# InterceptorRS232.net
KiCad netlist of a schematic drawn in Altium Designer
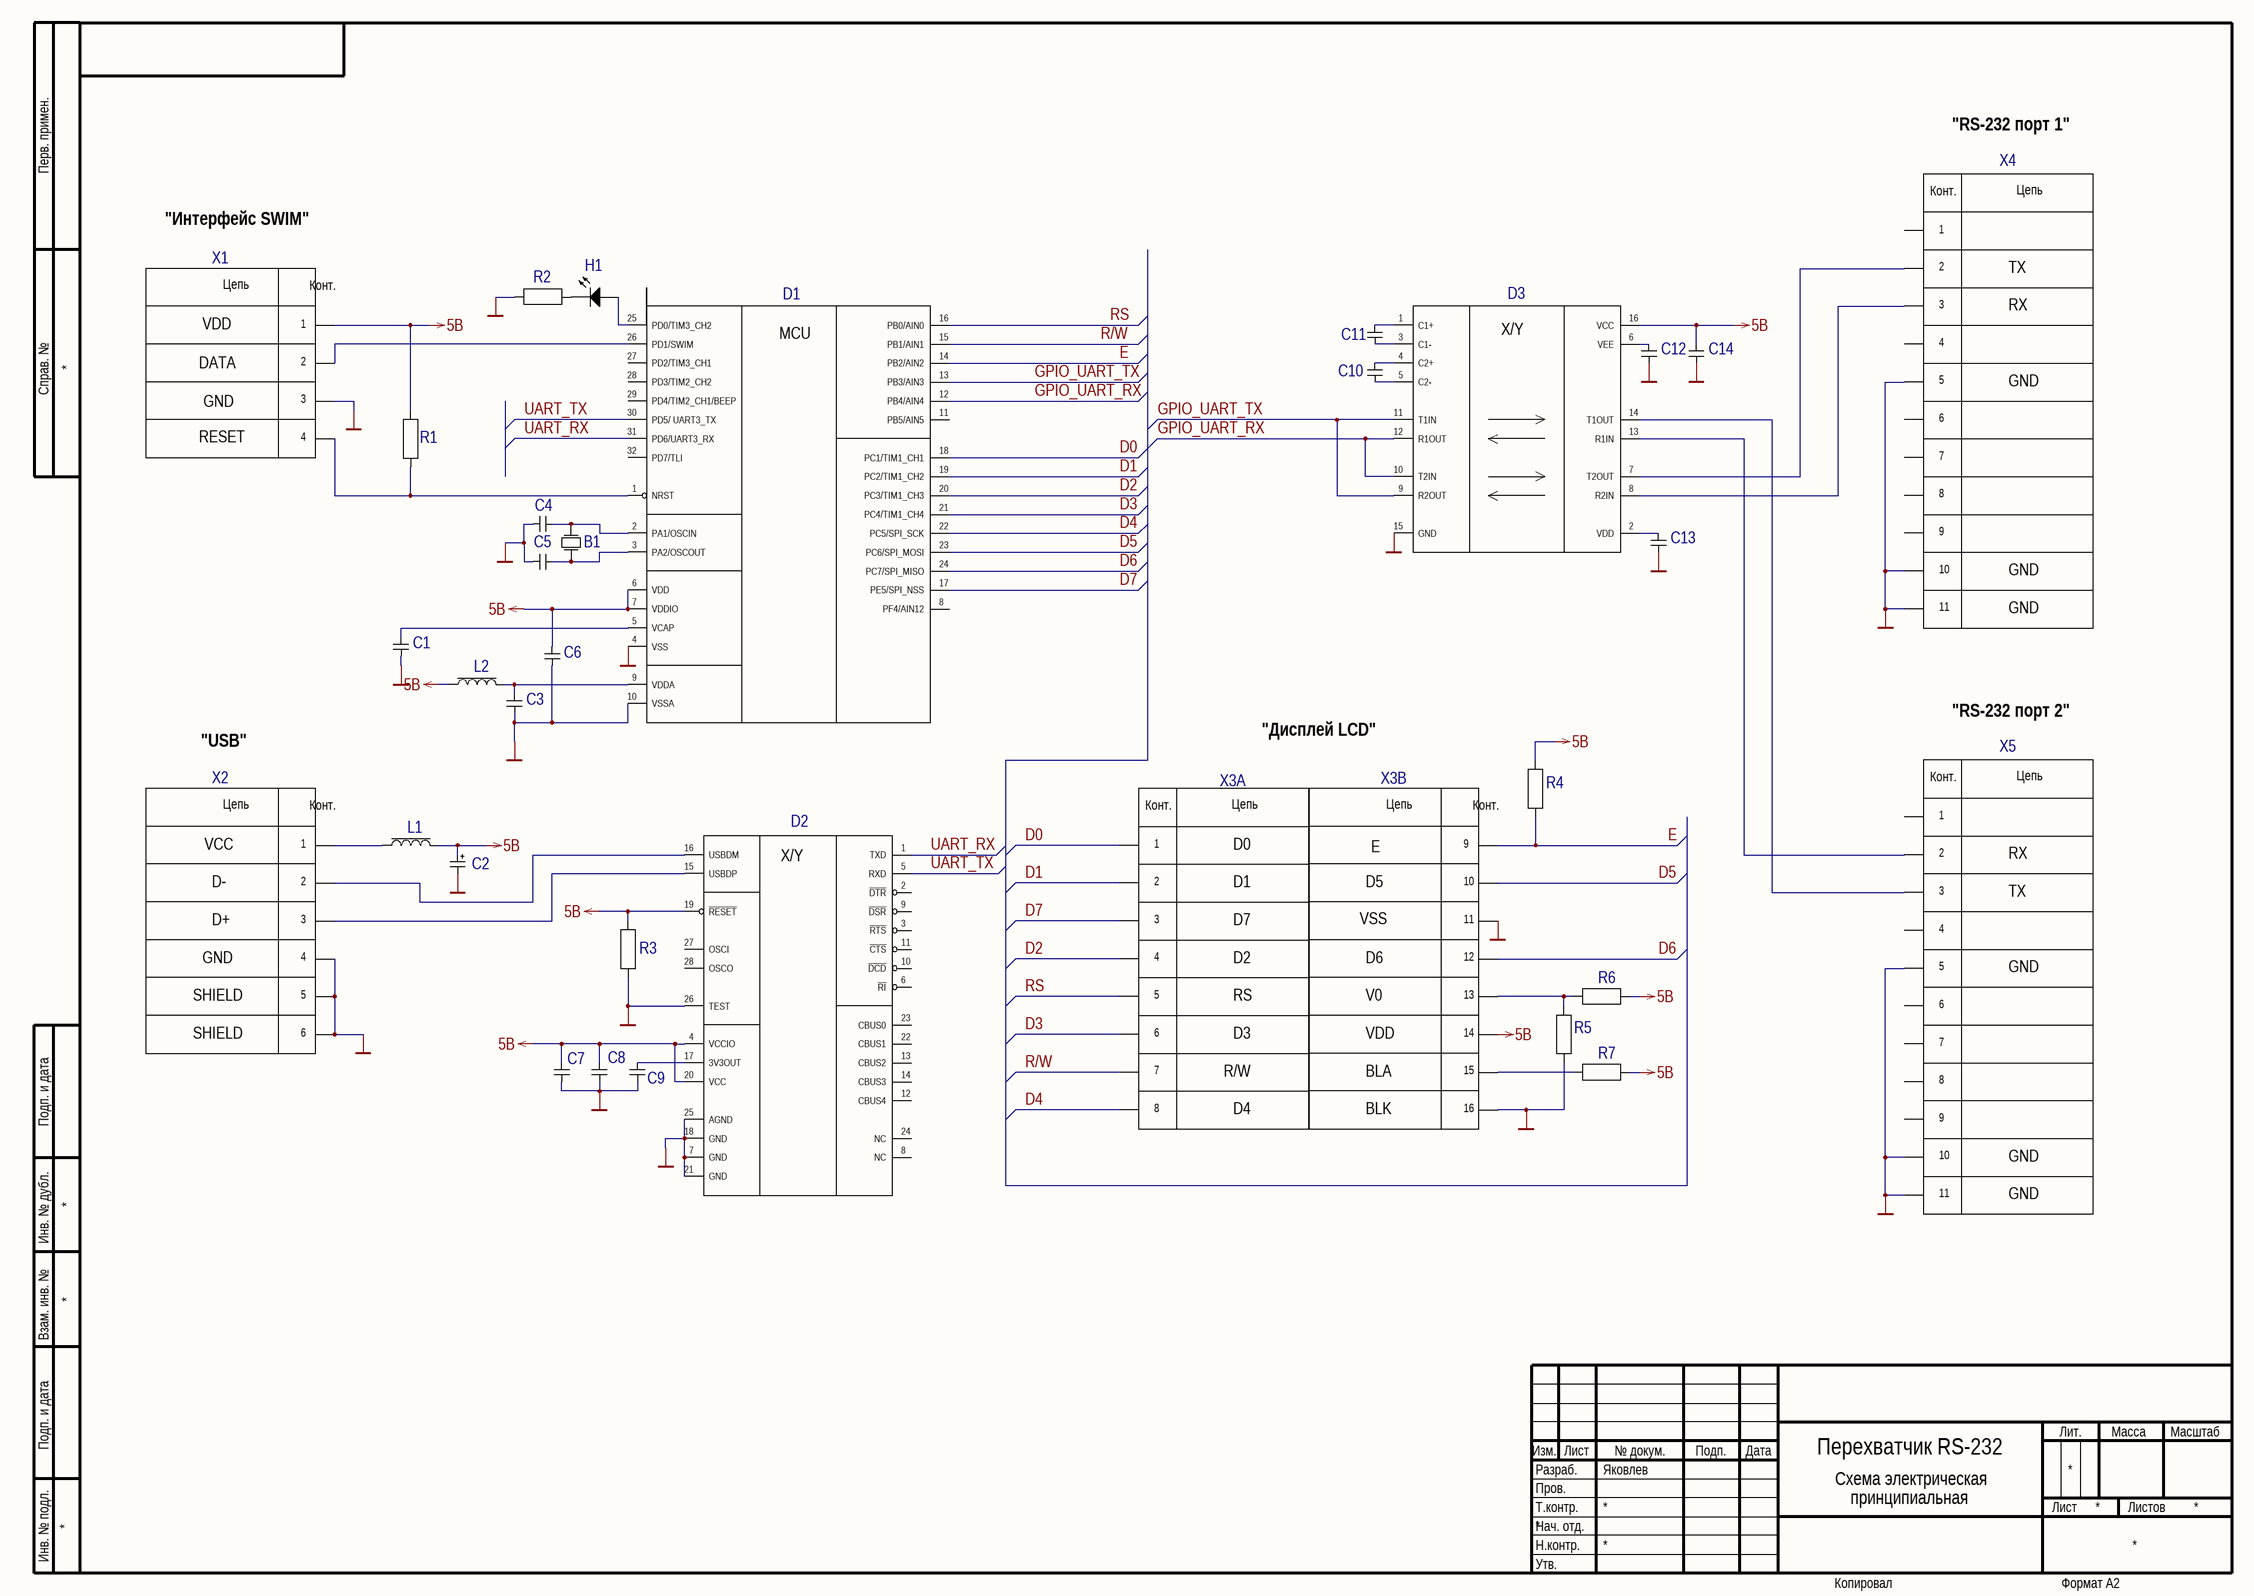
[diagram p0: InterceptorRS232.SchDoc]

(export (version "E")
  (design (tool "Eeschema 10.0.6"))
  (components
    (comp (ref "B1")
      (value "*")
      (footprint "CSM-7")
      (description "Crystal oscillator")
      (libsource (lib "InterceptorRS232") (part "CRYSTAL_OSCILLATOR"))
    )
    (comp (ref "C1")
      (value "~")
      (footprint "SMD-0805C")
      (description "Capacitor")
      (fields (field (name "PUBLISHER") "Altium Limited"))
      (libsource (lib "InterceptorRS232") (part "Cap"))
    )
    (comp (ref "C2")
      (value "Cap_el")
      (footprint "CAP_5x11")
      (description "Electrolytic capacitor")
      (fields (field (name "PUBLISHER") "Altium Limited"))
      (libsource (lib "InterceptorRS232") (part "Cap_el"))
    )
    (comp (ref "C3")
      (value "~")
      (footprint "SMD-0805C")
      (description "Capacitor")
      (fields (field (name "PUBLISHER") "Altium Limited"))
      (libsource (lib "InterceptorRS232") (part "Cap"))
    )
    (comp (ref "C4")
      (value "~")
      (footprint "SMD-0805C")
      (description "Capacitor")
      (fields (field (name "PUBLISHER") "Altium Limited"))
      (libsource (lib "InterceptorRS232") (part "Cap"))
    )
    (comp (ref "C5")
      (value "~")
      (footprint "SMD-0805C")
      (description "Capacitor")
      (fields (field (name "PUBLISHER") "Altium Limited"))
      (libsource (lib "InterceptorRS232") (part "Cap"))
    )
    (comp (ref "C6")
      (value "~")
      (footprint "SMD-0805C")
      (description "Capacitor")
      (fields (field (name "PUBLISHER") "Altium Limited"))
      (libsource (lib "InterceptorRS232") (part "Cap"))
    )
    (comp (ref "C7")
      (value "~")
      (footprint "SMD-0805C")
      (description "Capacitor")
      (fields (field (name "PUBLISHER") "Altium Limited"))
      (libsource (lib "InterceptorRS232") (part "Cap"))
    )
    (comp (ref "C8")
      (value "~")
      (footprint "SMD-0805C")
      (description "Capacitor")
      (fields (field (name "PUBLISHER") "Altium Limited"))
      (libsource (lib "InterceptorRS232") (part "Cap"))
    )
    (comp (ref "C9")
      (value "~")
      (footprint "SMD-0805C")
      (description "Capacitor")
      (fields (field (name "PUBLISHER") "Altium Limited"))
      (libsource (lib "InterceptorRS232") (part "Cap"))
    )
    (comp (ref "C10")
      (value "~")
      (footprint "SMD-0805C")
      (description "Capacitor")
      (fields (field (name "PUBLISHER") "Altium Limited"))
      (libsource (lib "InterceptorRS232") (part "Cap"))
    )
    (comp (ref "C11")
      (value "~")
      (footprint "SMD-0805C")
      (description "Capacitor")
      (fields (field (name "PUBLISHER") "Altium Limited"))
      (libsource (lib "InterceptorRS232") (part "Cap"))
    )
    (comp (ref "C12")
      (value "~")
      (footprint "SMD-0805C")
      (description "Capacitor")
      (fields (field (name "PUBLISHER") "Altium Limited"))
      (libsource (lib "InterceptorRS232") (part "Cap"))
    )
    (comp (ref "C13")
      (value "~")
      (footprint "SMD-0805C")
      (description "Capacitor")
      (fields (field (name "PUBLISHER") "Altium Limited"))
      (libsource (lib "InterceptorRS232") (part "Cap"))
    )
    (comp (ref "C14")
      (value "~")
      (footprint "SMD-0805C")
      (description "Capacitor")
      (fields (field (name "PUBLISHER") "Altium Limited"))
      (libsource (lib "InterceptorRS232") (part "Cap"))
    )
    (comp (ref "D1")
      (value "STM8S207K6T6C")
      (footprint "TQFP32_M")
      (description "8-bit STM8 MCU")
      (libsource (lib "InterceptorRS232") (part "STM8S207/STM8S208"))
    )
    (comp (ref "D2")
      (value "FT232RL-Reel")
      (footprint "SSOP-28_M")
      (description "USB UART Asynchronous Serial Data Transfer Chip, SSOP-28, Tape and Reel")
      (fields (field (name "PUBLISHER") "Altium Limited"))
      (libsource (lib "InterceptorRS232") (part "FT232RL-Reel"))
    )
    (comp (ref "D3")
      (value "MAX232EWE")
      (footprint "SOP-16 (2.54 mm)")
      (description "+5V Powered RS-232 Driver/Receiver")
      (fields (field (name "PUBLISHER") "Altium Limited"))
      (libsource (lib "InterceptorRS232") (part "MAX232EWE"))
    )
    (comp (ref "H1")
      (value "~")
      (footprint "LED_3mm")
      (description "Typical INFRARED GaAs LED")
      (fields (field (name "PUBLISHER") "Altium Limited"))
      (libsource (lib "InterceptorRS232") (part "LED0"))
    )
    (comp (ref "L1")
      (value "Inductor")
      (footprint "SMD-0805C")
      (fields (field (name "PUBLISHER") "Altium Limited"))
      (libsource (lib "InterceptorRS232") (part "Inductor"))
    )
    (comp (ref "L2")
      (value "Inductor")
      (footprint "SMD-0805C")
      (fields (field (name "PUBLISHER") "Altium Limited"))
      (libsource (lib "InterceptorRS232") (part "Inductor"))
    )
    (comp (ref "R1")
      (value "~")
      (footprint "SMD-0805-RES")
      (description "Resistor")
      (fields (field (name "PUBLISHER") "Altium Limited"))
      (libsource (lib "InterceptorRS232") (part "Res2"))
    )
    (comp (ref "R2")
      (value "~")
      (footprint "SMD-0805-RES")
      (description "Resistor")
      (fields (field (name "PUBLISHER") "Altium Limited"))
      (libsource (lib "") (part "Res2_1"))
    )
    (comp (ref "R3")
      (value "~")
      (footprint "SMD-0805-RES")
      (description "Resistor")
      (fields (field (name "PUBLISHER") "Altium Limited"))
      (libsource (lib "InterceptorRS232") (part "Res2"))
    )
    (comp (ref "R4")
      (value "~")
      (footprint "SMD-0805-RES")
      (description "Resistor")
      (fields (field (name "PUBLISHER") "Altium Limited"))
      (libsource (lib "") (part "Res2_2"))
    )
    (comp (ref "R5")
      (value "~")
      (footprint "SMD-0805-RES")
      (description "Resistor")
      (fields (field (name "PUBLISHER") "Altium Limited"))
      (libsource (lib "") (part "Res2_2"))
    )
    (comp (ref "R6")
      (value "~")
      (footprint "SMD-0805-RES")
      (description "Resistor")
      (fields (field (name "PUBLISHER") "Altium Limited"))
      (libsource (lib "") (part "Res2_1"))
    )
    (comp (ref "R7")
      (value "~")
      (footprint "SMD-0805-RES")
      (description "Resistor")
      (fields (field (name "PUBLISHER") "Altium Limited"))
      (libsource (lib "") (part "Res2_1"))
    )
    (comp (ref "X1")
      (value "*")
      (footprint "PLS-4")
      (description "PLS-4 connector")
      (libsource (lib "InterceptorRS232") (part "PLS-4"))
    )
    (comp (ref "X2")
      (value "*")
      (footprint "FCI USB 61729-0010BLF")
      (description "USB-B connector")
      (libsource (lib "InterceptorRS232") (part "USB-B"))
    )
    (comp (ref "X3")
      (value "*")
      (footprint "PLD2x8")
      (description "PLD2x8 connector")
      (libsource (lib "") (part "PLD2x8_1"))
    )
    (comp (ref "X4")
      (value "*")
      (footprint "DB-9F")
      (description "DB-9 connector")
      (libsource (lib "InterceptorRS232") (part "DB-9"))
    )
    (comp (ref "X5")
      (value "*")
      (footprint "DB-9M")
      (description "DB-9 connector")
      (libsource (lib "InterceptorRS232") (part "DB-9"))
    )
  )
  (nets
    (net (code "1") (name "/D0") (class "Default")
      (node (ref "D1") (pin "18") (pinfunction "PC1/TIM1_CH1_18") (pintype "passive"))
      (node (ref "X3") (pin "1") (pinfunction "1_1") (pintype "passive"))
    )
    (net (code "2") (name "/D1") (class "Default")
      (node (ref "D1") (pin "19") (pinfunction "PC2/TIM1_CH2_19") (pintype "passive"))
      (node (ref "X3") (pin "2") (pinfunction "2_2") (pintype "passive"))
    )
    (net (code "3") (name "/D2") (class "Default")
      (node (ref "D1") (pin "20") (pinfunction "PC3/TIM1_CH3_20") (pintype "passive"))
      (node (ref "X3") (pin "4") (pinfunction "4_4") (pintype "passive"))
    )
    (net (code "4") (name "/D3") (class "Default")
      (node (ref "D1") (pin "21") (pinfunction "PC4/TIM1_CH4_21") (pintype "passive"))
      (node (ref "X3") (pin "6") (pinfunction "6_6") (pintype "passive"))
    )
    (net (code "5") (name "/D4") (class "Default")
      (node (ref "D1") (pin "22") (pinfunction "PC5/SPI_SCK_22") (pintype "passive"))
      (node (ref "X3") (pin "8") (pinfunction "8_8") (pintype "passive"))
    )
    (net (code "6") (name "/D5") (class "Default")
      (node (ref "D1") (pin "23") (pinfunction "PC6/SPI_MOSI_23") (pintype "passive"))
      (node (ref "X3") (pin "10") (pinfunction "10_10") (pintype "passive"))
    )
    (net (code "7") (name "/D6") (class "Default")
      (node (ref "D1") (pin "24") (pinfunction "PC7/SPI_MISO_24") (pintype "passive"))
      (node (ref "X3") (pin "12") (pinfunction "12_12") (pintype "passive"))
    )
    (net (code "8") (name "/D7") (class "Default")
      (node (ref "D1") (pin "17") (pinfunction "PE5/SPI_NSS_17") (pintype "passive"))
      (node (ref "X3") (pin "3") (pinfunction "3_3") (pintype "passive"))
    )
    (net (code "9") (name "/E") (class "Default")
      (node (ref "D1") (pin "14") (pinfunction "PB2/AIN2_14") (pintype "passive"))
      (node (ref "R4") (pin "2") (pinfunction "2_2") (pintype "passive"))
      (node (ref "X3") (pin "9") (pinfunction "9_9") (pintype "passive"))
    )
    (net (code "10") (name "/GPIO_UART_RX") (class "Default")
      (node (ref "D1") (pin "12") (pinfunction "PB4/AIN4_12") (pintype "passive"))
      (node (ref "D3") (pin "10") (pinfunction "T2IN_10") (pintype "passive"))
      (node (ref "D3") (pin "12") (pinfunction "R1OUT_12") (pintype "passive"))
    )
    (net (code "11") (name "/GPIO_UART_TX") (class "Default")
      (node (ref "D1") (pin "13") (pinfunction "PB3/AIN3_13") (pintype "passive"))
      (node (ref "D3") (pin "11") (pinfunction "T1IN_11") (pintype "passive"))
      (node (ref "D3") (pin "9") (pinfunction "R2OUT_9") (pintype "passive"))
    )
    (net (code "12") (name "/RS") (class "Default")
      (node (ref "D1") (pin "16") (pinfunction "PB0/AIN0_16") (pintype "passive"))
      (node (ref "X3") (pin "5") (pinfunction "5_5") (pintype "passive"))
    )
    (net (code "13") (name "/R{slash}W") (class "Default")
      (node (ref "D1") (pin "15") (pinfunction "PB1/AIN1_15") (pintype "passive"))
      (node (ref "X3") (pin "7") (pinfunction "7_7") (pintype "passive"))
    )
    (net (code "14") (name "/UART_RX") (class "Default")
      (node (ref "D1") (pin "31") (pinfunction "PD6/UART3_RX_31") (pintype "passive"))
      (node (ref "D2") (pin "1") (pinfunction "TXD_1") (pintype "passive"))
    )
    (net (code "15") (name "/UART_TX") (class "Default")
      (node (ref "D1") (pin "30") (pinfunction "PD5/_UART3_TX_30") (pintype "passive"))
      (node (ref "D2") (pin "5") (pinfunction "RXD_5") (pintype "passive"))
    )
    (net (code "16") (name "5В") (class "Default")
      (node (ref "C14") (pin "2") (pinfunction "2_2") (pintype "passive"))
      (node (ref "C2") (pin "1") (pinfunction "1_1") (pintype "passive"))
      (node (ref "C6") (pin "2") (pinfunction "2_2") (pintype "passive"))
      (node (ref "C7") (pin "2") (pinfunction "2_2") (pintype "passive"))
      (node (ref "C8") (pin "2") (pinfunction "2_2") (pintype "passive"))
      (node (ref "D1") (pin "6") (pinfunction "VDD_6") (pintype "power_in"))
      (node (ref "D1") (pin "7") (pinfunction "VDDIO_7") (pintype "power_in"))
      (node (ref "D2") (pin "19") (pinfunction "~{RESET}_19") (pintype "passive"))
      (node (ref "D2") (pin "20") (pinfunction "VCC_20") (pintype "power_in"))
      (node (ref "D2") (pin "4") (pinfunction "VCCIO_4") (pintype "power_in"))
      (node (ref "D3") (pin "16") (pinfunction "VCC_16") (pintype "power_in"))
      (node (ref "L1") (pin "2") (pinfunction "2_2") (pintype "passive"))
      (node (ref "L2") (pin "1") (pinfunction "1_1") (pintype "passive"))
      (node (ref "R1") (pin "2") (pinfunction "2_2") (pintype "passive"))
      (node (ref "R3") (pin "2") (pinfunction "2_2") (pintype "passive"))
      (node (ref "R4") (pin "1") (pinfunction "1_1") (pintype "passive"))
      (node (ref "R6") (pin "1") (pinfunction "1_1") (pintype "passive"))
      (node (ref "R7") (pin "1") (pinfunction "1_1") (pintype "passive"))
      (node (ref "X1") (pin "1") (pinfunction "1_1") (pintype "passive"))
      (node (ref "X3") (pin "14") (pinfunction "14_14") (pintype "passive"))
    )
    (net (code "17") (name "GND") (class "Default")
      (node (ref "C1") (pin "1") (pinfunction "1_1") (pintype "passive"))
      (node (ref "C12") (pin "1") (pinfunction "1_1") (pintype "passive"))
      (node (ref "C13") (pin "1") (pinfunction "1_1") (pintype "passive"))
      (node (ref "C14") (pin "1") (pinfunction "1_1") (pintype "passive"))
      (node (ref "C2") (pin "2") (pinfunction "2_2") (pintype "passive"))
      (node (ref "C3") (pin "1") (pinfunction "1_1") (pintype "passive"))
      (node (ref "C4") (pin "2") (pinfunction "2_2") (pintype "passive"))
      (node (ref "C5") (pin "2") (pinfunction "2_2") (pintype "passive"))
      (node (ref "C6") (pin "1") (pinfunction "1_1") (pintype "passive"))
      (node (ref "C7") (pin "1") (pinfunction "1_1") (pintype "passive"))
      (node (ref "C8") (pin "1") (pinfunction "1_1") (pintype "passive"))
      (node (ref "C9") (pin "1") (pinfunction "1_1") (pintype "passive"))
      (node (ref "D1") (pin "10") (pinfunction "VSSA_10") (pintype "power_in"))
      (node (ref "D1") (pin "4") (pinfunction "VSS_4") (pintype "power_in"))
      (node (ref "D2") (pin "18") (pinfunction "GND_18") (pintype "power_in"))
      (node (ref "D2") (pin "21") (pinfunction "GND_21") (pintype "power_in"))
      (node (ref "D2") (pin "25") (pinfunction "AGND_25") (pintype "power_in"))
      (node (ref "D2") (pin "26") (pinfunction "TEST_26") (pintype "passive"))
      (node (ref "D2") (pin "7") (pinfunction "GND_7") (pintype "power_in"))
      (node (ref "D3") (pin "15") (pinfunction "GND_15") (pintype "power_in"))
      (node (ref "R2") (pin "2") (pinfunction "2_2") (pintype "passive"))
      (node (ref "R3") (pin "1") (pinfunction "1_1") (pintype "passive"))
      (node (ref "R5") (pin "2") (pinfunction "2_2") (pintype "passive"))
      (node (ref "X1") (pin "3") (pinfunction "3_3") (pintype "passive"))
      (node (ref "X2") (pin "4") (pinfunction "4_4") (pintype "passive"))
      (node (ref "X2") (pin "5") (pinfunction "5_5") (pintype "passive"))
      (node (ref "X2") (pin "6") (pinfunction "6_6") (pintype "passive"))
      (node (ref "X3") (pin "11") (pinfunction "11_11") (pintype "passive"))
      (node (ref "X3") (pin "16") (pinfunction "16_16") (pintype "passive"))
      (node (ref "X4") (pin "10") (pinfunction "10_10") (pintype "passive"))
      (node (ref "X4") (pin "11") (pinfunction "11_11") (pintype "passive"))
      (node (ref "X4") (pin "5") (pinfunction "5_5") (pintype "passive"))
      (node (ref "X5") (pin "10") (pinfunction "10_10") (pintype "passive"))
      (node (ref "X5") (pin "11") (pinfunction "11_11") (pintype "passive"))
      (node (ref "X5") (pin "5") (pinfunction "5_5") (pintype "passive"))
    )
    (net (code "18") (name "Net-(B1-OSCIN)") (class "Default")
      (node (ref "B1") (pin "1") (pinfunction "OSCIN_1") (pintype "passive"))
      (node (ref "C5") (pin "1") (pinfunction "1_1") (pintype "passive"))
      (node (ref "D1") (pin "3") (pinfunction "PA2/OSCOUT_3") (pintype "passive"))
    )
    (net (code "19") (name "Net-(B1-OSCOUT)") (class "Default")
      (node (ref "B1") (pin "2") (pinfunction "OSCOUT_2") (pintype "passive"))
      (node (ref "C4") (pin "1") (pinfunction "1_1") (pintype "passive"))
      (node (ref "D1") (pin "2") (pinfunction "PA1/OSCIN_2") (pintype "passive"))
    )
    (net (code "20") (name "Net-(D1-NRST)") (class "Default")
      (node (ref "D1") (pin "1") (pinfunction "NRST_1") (pintype "passive"))
      (node (ref "R1") (pin "1") (pinfunction "1_1") (pintype "passive"))
      (node (ref "X1") (pin "4") (pinfunction "4_4") (pintype "passive"))
    )
    (net (code "21") (name "Net-(D1-PD0{slash}TIM3_CH2)") (class "Default")
      (node (ref "D1") (pin "25") (pinfunction "PD0/TIM3_CH2_25") (pintype "passive"))
      (node (ref "H1") (pin "1") (pinfunction "A_1") (pintype "passive"))
    )
    (net (code "22") (name "Net-(D1-PD1{slash}SWIM)") (class "Default")
      (node (ref "D1") (pin "26") (pinfunction "PD1/SWIM_26") (pintype "passive"))
      (node (ref "X1") (pin "2") (pinfunction "2_2") (pintype "passive"))
    )
    (net (code "23") (name "Net-(D1-VCAP)") (class "Default")
      (node (ref "C1") (pin "2") (pinfunction "2_2") (pintype "passive"))
      (node (ref "D1") (pin "5") (pinfunction "VCAP_5") (pintype "power_in"))
    )
    (net (code "24") (name "Net-(D1-VDDA)") (class "Default")
      (node (ref "C3") (pin "2") (pinfunction "2_2") (pintype "passive"))
      (node (ref "D1") (pin "9") (pinfunction "VDDA_9") (pintype "power_in"))
      (node (ref "L2") (pin "2") (pinfunction "2_2") (pintype "passive"))
    )
    (net (code "25") (name "Net-(D2-3V3OUT)") (class "Default")
      (node (ref "C9") (pin "2") (pinfunction "2_2") (pintype "passive"))
      (node (ref "D2") (pin "17") (pinfunction "3V3OUT_17") (pintype "power_in"))
    )
    (net (code "26") (name "Net-(D2-USBDM)") (class "Default")
      (node (ref "D2") (pin "16") (pinfunction "USBDM_16") (pintype "passive"))
      (node (ref "X2") (pin "2") (pinfunction "2_2") (pintype "passive"))
    )
    (net (code "27") (name "Net-(D2-USBDP)") (class "Default")
      (node (ref "D2") (pin "15") (pinfunction "USBDP_15") (pintype "passive"))
      (node (ref "X2") (pin "3") (pinfunction "3_3") (pintype "passive"))
    )
    (net (code "28") (name "Net-(D3-C1+)") (class "Default")
      (node (ref "C11") (pin "2") (pinfunction "2_2") (pintype "passive"))
      (node (ref "D3") (pin "1") (pinfunction "C1+_1") (pintype "passive"))
    )
    (net (code "29") (name "Net-(D3-C1-)") (class "Default")
      (node (ref "C11") (pin "1") (pinfunction "1_1") (pintype "passive"))
      (node (ref "D3") (pin "3") (pinfunction "C1-_3") (pintype "passive"))
    )
    (net (code "30") (name "Net-(D3-C2+)") (class "Default")
      (node (ref "C10") (pin "2") (pinfunction "2_2") (pintype "passive"))
      (node (ref "D3") (pin "4") (pinfunction "C2+_4") (pintype "passive"))
    )
    (net (code "31") (name "Net-(D3-C2-)") (class "Default")
      (node (ref "C10") (pin "1") (pinfunction "1_1") (pintype "passive"))
      (node (ref "D3") (pin "5") (pinfunction "C2-_5") (pintype "passive"))
    )
    (net (code "32") (name "Net-(D3-R1IN)") (class "Default")
      (node (ref "D3") (pin "13") (pinfunction "R1IN_13") (pintype "passive"))
      (node (ref "X5") (pin "2") (pinfunction "2_2") (pintype "passive"))
    )
    (net (code "33") (name "Net-(D3-R2IN)") (class "Default")
      (node (ref "D3") (pin "8") (pinfunction "R2IN_8") (pintype "passive"))
      (node (ref "X4") (pin "3") (pinfunction "3_3") (pintype "passive"))
    )
    (net (code "34") (name "Net-(D3-T1OUT)") (class "Default")
      (node (ref "D3") (pin "14") (pinfunction "T1OUT_14") (pintype "passive"))
      (node (ref "X5") (pin "3") (pinfunction "3_3") (pintype "passive"))
    )
    (net (code "35") (name "Net-(D3-T2OUT)") (class "Default")
      (node (ref "D3") (pin "7") (pinfunction "T2OUT_7") (pintype "passive"))
      (node (ref "X4") (pin "2") (pinfunction "2_2") (pintype "passive"))
    )
    (net (code "36") (name "Net-(D3-VDD)") (class "Default")
      (node (ref "C13") (pin "2") (pinfunction "2_2") (pintype "passive"))
      (node (ref "D3") (pin "2") (pinfunction "VDD_2") (pintype "power_in"))
    )
    (net (code "37") (name "Net-(D3-VEE)") (class "Default")
      (node (ref "C12") (pin "2") (pinfunction "2_2") (pintype "passive"))
      (node (ref "D3") (pin "6") (pinfunction "VEE_6") (pintype "power_in"))
    )
    (net (code "38") (name "Net-(H1-K)") (class "Default")
      (node (ref "H1") (pin "2") (pinfunction "K_2") (pintype "passive"))
      (node (ref "R2") (pin "1") (pinfunction "1_1") (pintype "passive"))
    )
    (net (code "39") (name "Net-(L1-Pad1)") (class "Default")
      (node (ref "L1") (pin "1") (pinfunction "1_1") (pintype "passive"))
      (node (ref "X2") (pin "1") (pinfunction "1_1") (pintype "passive"))
    )
    (net (code "40") (name "Net-(R5-Pad1)") (class "Default")
      (node (ref "R5") (pin "1") (pinfunction "1_1") (pintype "passive"))
      (node (ref "R6") (pin "2") (pinfunction "2_2") (pintype "passive"))
      (node (ref "X3") (pin "13") (pinfunction "13_13") (pintype "passive"))
    )
    (net (code "41") (name "Net-(R7-Pad2)") (class "Default")
      (node (ref "R7") (pin "2") (pinfunction "2_2") (pintype "passive"))
      (node (ref "X3") (pin "15") (pinfunction "15_15") (pintype "passive"))
    )
    (net (code "42") (name "unconnected-(D1-PB5{slash}AIN5-Pad11)") (class "Default")
      (node (ref "D1") (pin "11") (pinfunction "PB5/AIN5_11") (pintype "passive"))
    )
    (net (code "43") (name "unconnected-(D1-PD2{slash}TIM3_CH1-Pad27)") (class "Default")
      (node (ref "D1") (pin "27") (pinfunction "PD2/TIM3_CH1_27") (pintype "passive"))
    )
    (net (code "44") (name "unconnected-(D1-PD3{slash}TIM2_CH2-Pad28)") (class "Default")
      (node (ref "D1") (pin "28") (pinfunction "PD3/TIM2_CH2_28") (pintype "passive"))
    )
    (net (code "45") (name "unconnected-(D1-PD4{slash}TIM2_CH1{slash}BEEP-Pad29)") (class "Default")
      (node (ref "D1") (pin "29") (pinfunction "PD4/TIM2_CH1/BEEP_29") (pintype "passive"))
    )
    (net (code "46") (name "unconnected-(D1-PD7{slash}TLI-Pad32)") (class "Default")
      (node (ref "D1") (pin "32") (pinfunction "PD7/TLI_32") (pintype "passive"))
    )
    (net (code "47") (name "unconnected-(D1-PF4{slash}AIN12-Pad8)") (class "Default")
      (node (ref "D1") (pin "8") (pinfunction "PF4/AIN12_8") (pintype "passive"))
    )
    (net (code "48") (name "unconnected-(D2-CBUS0-Pad23)") (class "Default")
      (node (ref "D2") (pin "23") (pinfunction "CBUS0_23") (pintype "passive"))
    )
    (net (code "49") (name "unconnected-(D2-CBUS1-Pad22)") (class "Default")
      (node (ref "D2") (pin "22") (pinfunction "CBUS1_22") (pintype "passive"))
    )
    (net (code "50") (name "unconnected-(D2-CBUS2-Pad13)") (class "Default")
      (node (ref "D2") (pin "13") (pinfunction "CBUS2_13") (pintype "passive"))
    )
    (net (code "51") (name "unconnected-(D2-CBUS3-Pad14)") (class "Default")
      (node (ref "D2") (pin "14") (pinfunction "CBUS3_14") (pintype "passive"))
    )
    (net (code "52") (name "unconnected-(D2-CBUS4-Pad12)") (class "Default")
      (node (ref "D2") (pin "12") (pinfunction "CBUS4_12") (pintype "passive"))
    )
    (net (code "53") (name "unconnected-(D2-NC-Pad8)") (class "Default")
      (node (ref "D2") (pin "8") (pinfunction "NC_8") (pintype "passive"))
    )
    (net (code "54") (name "unconnected-(D2-NC-Pad24)") (class "Default")
      (node (ref "D2") (pin "24") (pinfunction "NC_24") (pintype "passive"))
    )
    (net (code "55") (name "unconnected-(D2-OSCI-Pad27)") (class "Default")
      (node (ref "D2") (pin "27") (pinfunction "OSCI_27") (pintype "passive"))
    )
    (net (code "56") (name "unconnected-(D2-OSCO-Pad28)") (class "Default")
      (node (ref "D2") (pin "28") (pinfunction "OSCO_28") (pintype "passive"))
    )
    (net (code "57") (name "unconnected-(D2-~{CTS}-Pad11)") (class "Default")
      (node (ref "D2") (pin "11") (pinfunction "~{CTS}_11") (pintype "passive"))
    )
    (net (code "58") (name "unconnected-(D2-~{DCD}-Pad10)") (class "Default")
      (node (ref "D2") (pin "10") (pinfunction "~{DCD}_10") (pintype "passive"))
    )
    (net (code "59") (name "unconnected-(D2-~{DSR}-Pad9)") (class "Default")
      (node (ref "D2") (pin "9") (pinfunction "~{DSR}_9") (pintype "passive"))
    )
    (net (code "60") (name "unconnected-(D2-~{DTR}-Pad2)") (class "Default")
      (node (ref "D2") (pin "2") (pinfunction "~{DTR}_2") (pintype "passive"))
    )
    (net (code "61") (name "unconnected-(D2-~{RI}-Pad6)") (class "Default")
      (node (ref "D2") (pin "6") (pinfunction "~{RI}_6") (pintype "passive"))
    )
    (net (code "62") (name "unconnected-(D2-~{RTS}-Pad3)") (class "Default")
      (node (ref "D2") (pin "3") (pinfunction "~{RTS}_3") (pintype "passive"))
    )
    (net (code "63") (name "unconnected-(X4-Pad1)") (class "Default")
      (node (ref "X4") (pin "1") (pinfunction "1_1") (pintype "passive"))
    )
    (net (code "64") (name "unconnected-(X4-Pad4)") (class "Default")
      (node (ref "X4") (pin "4") (pinfunction "4_4") (pintype "passive"))
    )
    (net (code "65") (name "unconnected-(X4-Pad6)") (class "Default")
      (node (ref "X4") (pin "6") (pinfunction "6_6") (pintype "passive"))
    )
    (net (code "66") (name "unconnected-(X4-Pad7)") (class "Default")
      (node (ref "X4") (pin "7") (pinfunction "7_7") (pintype "passive"))
    )
    (net (code "67") (name "unconnected-(X4-Pad8)") (class "Default")
      (node (ref "X4") (pin "8") (pinfunction "8_8") (pintype "passive"))
    )
    (net (code "68") (name "unconnected-(X4-Pad9)") (class "Default")
      (node (ref "X4") (pin "9") (pinfunction "9_9") (pintype "passive"))
    )
    (net (code "69") (name "unconnected-(X5-Pad1)") (class "Default")
      (node (ref "X5") (pin "1") (pinfunction "1_1") (pintype "passive"))
    )
    (net (code "70") (name "unconnected-(X5-Pad4)") (class "Default")
      (node (ref "X5") (pin "4") (pinfunction "4_4") (pintype "passive"))
    )
    (net (code "71") (name "unconnected-(X5-Pad6)") (class "Default")
      (node (ref "X5") (pin "6") (pinfunction "6_6") (pintype "passive"))
    )
    (net (code "72") (name "unconnected-(X5-Pad7)") (class "Default")
      (node (ref "X5") (pin "7") (pinfunction "7_7") (pintype "passive"))
    )
    (net (code "73") (name "unconnected-(X5-Pad8)") (class "Default")
      (node (ref "X5") (pin "8") (pinfunction "8_8") (pintype "passive"))
    )
    (net (code "74") (name "unconnected-(X5-Pad9)") (class "Default")
      (node (ref "X5") (pin "9") (pinfunction "9_9") (pintype "passive"))
    )
  )
)
